# Snip_MCU.net
KiCad netlist of a schematic drawn in Altium Designer
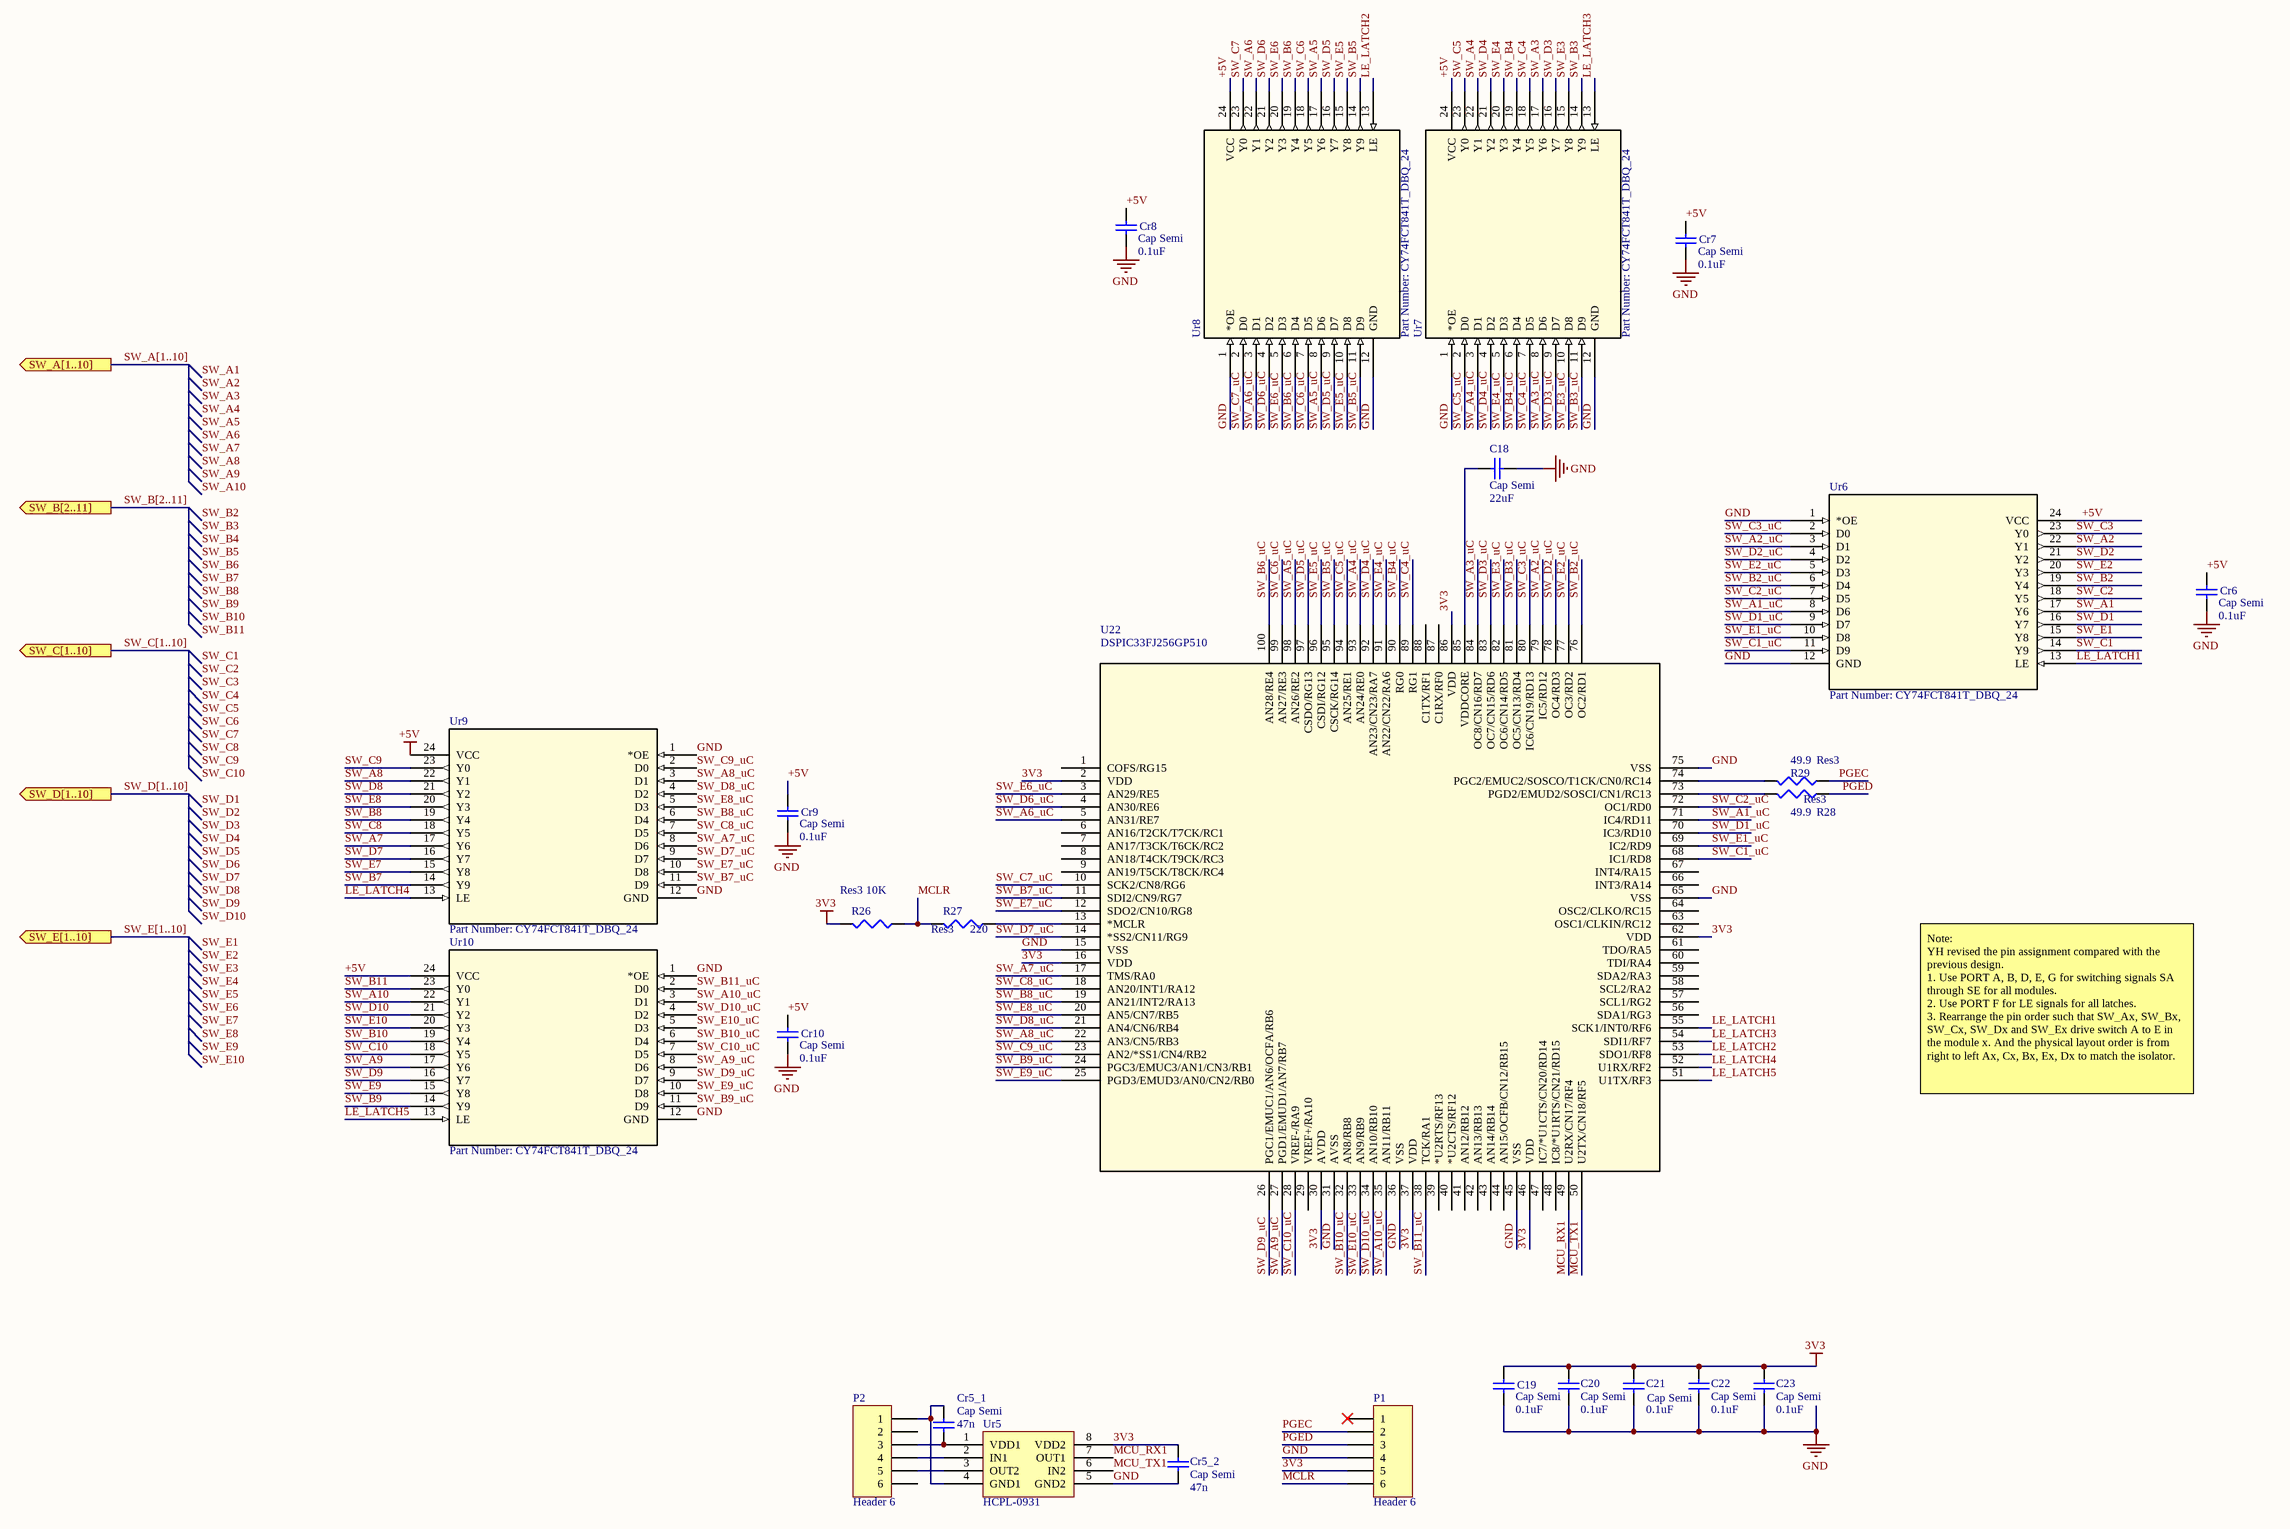
[diagram p0: Snip_MCU.SchDoc]

(export (version "E")
  (design (tool "Eeschema 10.0.6"))
  (components
    (comp (ref "C18")
      (value "Cap Semi")
      (footprint "0805")
      (description "Capacitor (Semiconductor SIM Model)")
      (fields (field (name "ALTIUM_VALUE") "22uF") (field (name "PUBLISHER") "Altium Limited"))
      (libsource (lib "SCMLI_V3_1") (part "Cap Semi"))
    )
    (comp (ref "C19")
      (value "Cap Semi")
      (footprint "1608[0603]")
      (description "Capacitor (Semiconductor SIM Model)")
      (fields (field (name "ALTIUM_VALUE") "0.1uF") (field (name "PUBLISHER") "Altium Limited"))
      (libsource (lib "Miscellaneous Devices") (part "Cap Semi"))
    )
    (comp (ref "C20")
      (value "Cap Semi")
      (footprint "1608[0603]")
      (description "Capacitor (Semiconductor SIM Model)")
      (fields (field (name "ALTIUM_VALUE") "0.1uF") (field (name "PUBLISHER") "Altium Limited"))
      (libsource (lib "Miscellaneous Devices") (part "Cap Semi"))
    )
    (comp (ref "C21")
      (value "Cap Semi")
      (footprint "1608[0603]")
      (description "Capacitor (Semiconductor SIM Model)")
      (fields (field (name "ALTIUM_VALUE") "0.1uF") (field (name "PUBLISHER") "Altium Limited"))
      (libsource (lib "Miscellaneous Devices") (part "Cap Semi"))
    )
    (comp (ref "C22")
      (value "Cap Semi")
      (footprint "1608[0603]")
      (description "Capacitor (Semiconductor SIM Model)")
      (fields (field (name "ALTIUM_VALUE") "0.1uF") (field (name "PUBLISHER") "Altium Limited"))
      (libsource (lib "Miscellaneous Devices") (part "Cap Semi"))
    )
    (comp (ref "C23")
      (value "Cap Semi")
      (footprint "1608[0603]")
      (description "Capacitor (Semiconductor SIM Model)")
      (fields (field (name "ALTIUM_VALUE") "0.1uF") (field (name "PUBLISHER") "Altium Limited"))
      (libsource (lib "Miscellaneous Devices") (part "Cap Semi"))
    )
    (comp (ref "Cr5_1")
      (value "Cap Semi")
      (footprint "C1206")
      (description "Capacitor (Semiconductor SIM Model)")
      (fields (field (name "ALTIUM_VALUE") "47n") (field (name "PUBLISHER") "Altium Limited"))
      (libsource (lib "SCMLI_V3_1") (part "Cap Semi"))
    )
    (comp (ref "Cr5_2")
      (value "Cap Semi")
      (footprint "C1206")
      (description "Capacitor (Semiconductor SIM Model)")
      (fields (field (name "ALTIUM_VALUE") "47n") (field (name "PUBLISHER") "Altium Limited"))
      (libsource (lib "SCMLI_V3_1") (part "Cap Semi"))
    )
    (comp (ref "Cr6")
      (value "Cap Semi")
      (footprint "1608[0603]")
      (description "Capacitor (Semiconductor SIM Model)")
      (fields (field (name "ALTIUM_VALUE") "0.1uF") (field (name "PUBLISHER") "Altium Limited"))
      (libsource (lib "Miscellaneous Devices") (part "Cap Semi"))
    )
    (comp (ref "Cr7")
      (value "Cap Semi")
      (footprint "1608[0603]")
      (description "Capacitor (Semiconductor SIM Model)")
      (fields (field (name "ALTIUM_VALUE") "0.1uF") (field (name "PUBLISHER") "Altium Limited"))
      (libsource (lib "Miscellaneous Devices") (part "Cap Semi"))
    )
    (comp (ref "Cr8")
      (value "Cap Semi")
      (footprint "1608[0603]")
      (description "Capacitor (Semiconductor SIM Model)")
      (fields (field (name "ALTIUM_VALUE") "0.1uF") (field (name "PUBLISHER") "Altium Limited"))
      (libsource (lib "Miscellaneous Devices") (part "Cap Semi"))
    )
    (comp (ref "Cr9")
      (value "Cap Semi")
      (footprint "1608[0603]")
      (description "Capacitor (Semiconductor SIM Model)")
      (fields (field (name "ALTIUM_VALUE") "0.1uF") (field (name "PUBLISHER") "Altium Limited"))
      (libsource (lib "Miscellaneous Devices") (part "Cap Semi"))
    )
    (comp (ref "Cr10")
      (value "Cap Semi")
      (footprint "1608[0603]")
      (description "Capacitor (Semiconductor SIM Model)")
      (fields (field (name "ALTIUM_VALUE") "0.1uF") (field (name "PUBLISHER") "Altium Limited"))
      (libsource (lib "Miscellaneous Devices") (part "Cap Semi"))
    )
    (comp (ref "P1")
      (value "Header 6")
      (footprint "HDR1X6")
      (description "Header, 6-Pin")
      (fields (field (name "PUBLISHER") "Altium Limited"))
      (libsource (lib "Miscellaneous Connectors") (part "Header 6"))
    )
    (comp (ref "P2")
      (value "Header 6")
      (footprint "HDR1X6")
      (description "Header, 6-Pin")
      (fields (field (name "PUBLISHER") "Altium Limited"))
      (libsource (lib "SCMLI_V3_1") (part "Header 6"))
    )
    (comp (ref "R26")
      (value "Res3")
      (footprint "J1-0603")
      (description "Resistor")
      (fields (field (name "ALTIUM_VALUE") "10K") (field (name "PUBLISHER") "Altium Limited"))
      (libsource (lib "Miscellaneous Devices") (part "Res3"))
    )
    (comp (ref "R27")
      (value "Res3")
      (footprint "J1-0603")
      (description "Resistor")
      (fields (field (name "ALTIUM_VALUE") "220") (field (name "PUBLISHER") "Altium Limited"))
      (libsource (lib "Miscellaneous Devices") (part "Res3"))
    )
    (comp (ref "R28")
      (value "Res3")
      (footprint "J1-0603")
      (description "Resistor")
      (fields (field (name "ALTIUM_VALUE") "49.9") (field (name "PUBLISHER") "Altium Limited"))
      (libsource (lib "Miscellaneous Devices") (part "Res3"))
    )
    (comp (ref "R29")
      (value "Res3")
      (footprint "J1-0603")
      (description "Resistor")
      (fields (field (name "ALTIUM_VALUE") "49.9") (field (name "PUBLISHER") "Altium Limited"))
      (libsource (lib "Miscellaneous Devices") (part "Res3"))
    )
    (comp (ref "U22")
      (value "DSPIC33FJ256GP510")
      (footprint "TQFP100_12x12MC-")
      (description "No Description Available")
      (fields (field (name "COPYRIGHT") "Copyright (C) 2018 Accelerated Designs. All rights reserved"))
      (libsource (lib "SCMLI_V3_1") (part "DSPIC33FJ256GP510"))
    )
    (comp (ref "Ur5")
      (value "HCPL-0931")
      (footprint "SOIC-8")
      (libsource (lib "SCMLI_V3_1") (part "HCPL-0931"))
    )
    (comp (ref "Ur6")
      (value "Part Number: CY74FCT841T_DBQ_24")
      (footprint "DBQ24")
      (description "10-Bit Bus-Interface D-Type Latches with 3-State Outputs")
      (fields
        (field (name "MANUFACTURER") "Texas Instruments")
        (field (name "GENERIC_PART_NUMBER") "CY74FCT841T")
        (field (name "COPYRIGHT") "Copyright (C) 2018 Accelerated Designs. All rights reserved")
      )
      (libsource (lib "") (part "CY74FCT841T_DBQ__2"))
    )
    (comp (ref "Ur7")
      (value "Part Number: CY74FCT841T_DBQ_24")
      (footprint "DBQ24")
      (description "10-Bit Bus-Interface D-Type Latches with 3-State Outputs")
      (fields
        (field (name "MANUFACTURER") "Texas Instruments")
        (field (name "GENERIC_PART_NUMBER") "CY74FCT841T")
        (field (name "COPYRIGHT") "Copyright (C) 2018 Accelerated Designs. All rights reserved")
      )
      (libsource (lib "") (part "CY74FCT841T_DBQ__1"))
    )
    (comp (ref "Ur8")
      (value "Part Number: CY74FCT841T_DBQ_24")
      (footprint "DBQ24")
      (description "10-Bit Bus-Interface D-Type Latches with 3-State Outputs")
      (fields
        (field (name "MANUFACTURER") "Texas Instruments")
        (field (name "GENERIC_PART_NUMBER") "CY74FCT841T")
        (field (name "COPYRIGHT") "Copyright (C) 2018 Accelerated Designs. All rights reserved")
      )
      (libsource (lib "") (part "CY74FCT841T_DBQ__1"))
    )
    (comp (ref "Ur9")
      (value "Part Number: CY74FCT841T_DBQ_24")
      (footprint "DBQ24")
      (description "10-Bit Bus-Interface D-Type Latches with 3-State Outputs")
      (fields
        (field (name "MANUFACTURER") "Texas Instruments")
        (field (name "GENERIC_PART_NUMBER") "CY74FCT841T")
        (field (name "COPYRIGHT") "Copyright (C) 2018 Accelerated Designs. All rights reserved")
      )
      (libsource (lib "SCMLI_V3_1") (part "CY74FCT841T_DBQ_"))
    )
    (comp (ref "Ur10")
      (value "Part Number: CY74FCT841T_DBQ_24")
      (footprint "DBQ24")
      (description "10-Bit Bus-Interface D-Type Latches with 3-State Outputs")
      (fields
        (field (name "MANUFACTURER") "Texas Instruments")
        (field (name "GENERIC_PART_NUMBER") "CY74FCT841T")
        (field (name "COPYRIGHT") "Copyright (C) 2018 Accelerated Designs. All rights reserved")
      )
      (libsource (lib "SCMLI_V3_1") (part "CY74FCT841T_DBQ_"))
    )
  )
  (nets
    (net (code "1") (name "+5V") (class "Default")
      (node (ref "Cr10") (pin "2") (pinfunction "2_2") (pintype "passive"))
      (node (ref "Cr6") (pin "2") (pinfunction "2_2") (pintype "passive"))
      (node (ref "Cr7") (pin "2") (pinfunction "2_2") (pintype "passive"))
      (node (ref "Cr8") (pin "2") (pinfunction "2_2") (pintype "passive"))
      (node (ref "Cr9") (pin "2") (pinfunction "2_2") (pintype "passive"))
      (node (ref "Ur10") (pin "24") (pinfunction "VCC_24") (pintype "power_in"))
      (node (ref "Ur6") (pin "24") (pinfunction "VCC_24") (pintype "power_in"))
      (node (ref "Ur7") (pin "24") (pinfunction "VCC_24") (pintype "power_in"))
      (node (ref "Ur8") (pin "24") (pinfunction "VCC_24") (pintype "power_in"))
      (node (ref "Ur9") (pin "24") (pinfunction "VCC_24") (pintype "power_in"))
    )
    (net (code "2") (name "/LE_LATCH1") (class "Default")
      (node (ref "U22") (pin "55") (pinfunction "SCK1/INT0/RF6_55") (pintype "passive"))
      (node (ref "Ur6") (pin "13") (pinfunction "LE_13") (pintype "input"))
    )
    (net (code "3") (name "/LE_LATCH2") (class "Default")
      (node (ref "U22") (pin "53") (pinfunction "SDO1/RF8_53") (pintype "passive"))
      (node (ref "Ur8") (pin "13") (pinfunction "LE_13") (pintype "input"))
    )
    (net (code "4") (name "/LE_LATCH3") (class "Default")
      (node (ref "U22") (pin "54") (pinfunction "SDI1/RF7_54") (pintype "passive"))
      (node (ref "Ur7") (pin "13") (pinfunction "LE_13") (pintype "input"))
    )
    (net (code "5") (name "/LE_LATCH4") (class "Default")
      (node (ref "U22") (pin "52") (pinfunction "U1RX/RF2_52") (pintype "passive"))
      (node (ref "Ur9") (pin "13") (pinfunction "LE_13") (pintype "input"))
    )
    (net (code "6") (name "/LE_LATCH5") (class "Default")
      (node (ref "U22") (pin "51") (pinfunction "U1TX/RF3_51") (pintype "passive"))
      (node (ref "Ur10") (pin "13") (pinfunction "LE_13") (pintype "input"))
    )
    (net (code "7") (name "/MCLR") (class "Default")
      (node (ref "P1") (pin "6") (pinfunction "6_6") (pintype "passive"))
      (node (ref "R26") (pin "1") (pinfunction "1_1") (pintype "passive"))
      (node (ref "R27") (pin "2") (pinfunction "2_2") (pintype "passive"))
    )
    (net (code "8") (name "/MCU_RX1") (class "Default")
      (node (ref "U22") (pin "49") (pinfunction "U2RX/CN17/RF4_49") (pintype "passive"))
      (node (ref "Ur5") (pin "7") (pinfunction "OUT1_7") (pintype "passive"))
    )
    (net (code "9") (name "/MCU_TX1") (class "Default")
      (node (ref "U22") (pin "50") (pinfunction "U2TX/CN18/RF5_50") (pintype "passive"))
      (node (ref "Ur5") (pin "6") (pinfunction "IN2_6") (pintype "passive"))
    )
    (net (code "10") (name "/PGEC") (class "Default")
      (node (ref "P1") (pin "2") (pinfunction "2_2") (pintype "passive"))
      (node (ref "R29") (pin "1") (pinfunction "1_1") (pintype "passive"))
    )
    (net (code "11") (name "/PGED") (class "Default")
      (node (ref "P1") (pin "3") (pinfunction "3_3") (pintype "passive"))
      (node (ref "R28") (pin "1") (pinfunction "1_1") (pintype "passive"))
    )
    (net (code "12") (name "/SW_A1") (class "Default")
      (node (ref "Ur6") (pin "17") (pinfunction "Y6_17") (pintype "output"))
    )
    (net (code "13") (name "/SW_A1_uC") (class "Default")
      (node (ref "U22") (pin "71") (pinfunction "IC4/RD11_71") (pintype "passive"))
      (node (ref "Ur6") (pin "8") (pinfunction "D6_8") (pintype "input"))
    )
    (net (code "14") (name "/SW_A2") (class "Default")
      (node (ref "Ur6") (pin "22") (pinfunction "Y1_22") (pintype "output"))
    )
    (net (code "15") (name "/SW_A2_uC") (class "Default")
      (node (ref "U22") (pin "79") (pinfunction "IC5/RD12_79") (pintype "passive"))
      (node (ref "Ur6") (pin "3") (pinfunction "D1_3") (pintype "input"))
    )
    (net (code "16") (name "/SW_A3") (class "Default")
      (node (ref "Ur7") (pin "17") (pinfunction "Y6_17") (pintype "output"))
    )
    (net (code "17") (name "/SW_A3_uC") (class "Default")
      (node (ref "U22") (pin "84") (pinfunction "OC8/CN16/RD7_84") (pintype "passive"))
      (node (ref "Ur7") (pin "8") (pinfunction "D6_8") (pintype "input"))
    )
    (net (code "18") (name "/SW_A4") (class "Default")
      (node (ref "Ur7") (pin "22") (pinfunction "Y1_22") (pintype "output"))
    )
    (net (code "19") (name "/SW_A4_uC") (class "Default")
      (node (ref "U22") (pin "93") (pinfunction "AN24/RE0_93") (pintype "passive"))
      (node (ref "Ur7") (pin "3") (pinfunction "D1_3") (pintype "input"))
    )
    (net (code "20") (name "/SW_A5") (class "Default")
      (node (ref "Ur8") (pin "17") (pinfunction "Y6_17") (pintype "output"))
    )
    (net (code "21") (name "/SW_A5_uC") (class "Default")
      (node (ref "U22") (pin "98") (pinfunction "AN26/RE2_98") (pintype "passive"))
      (node (ref "Ur8") (pin "8") (pinfunction "D6_8") (pintype "input"))
    )
    (net (code "22") (name "/SW_A6") (class "Default")
      (node (ref "Ur8") (pin "22") (pinfunction "Y1_22") (pintype "output"))
    )
    (net (code "23") (name "/SW_A6_uC") (class "Default")
      (node (ref "U22") (pin "5") (pinfunction "AN31/RE7_5") (pintype "passive"))
      (node (ref "Ur8") (pin "3") (pinfunction "D1_3") (pintype "input"))
    )
    (net (code "24") (name "/SW_A7") (class "Default")
      (node (ref "Ur9") (pin "17") (pinfunction "Y6_17") (pintype "output"))
    )
    (net (code "25") (name "/SW_A7_uC") (class "Default")
      (node (ref "U22") (pin "17") (pinfunction "TMS/RA0_17") (pintype "passive"))
      (node (ref "Ur9") (pin "8") (pinfunction "D6_8") (pintype "input"))
    )
    (net (code "26") (name "/SW_A8") (class "Default")
      (node (ref "Ur9") (pin "22") (pinfunction "Y1_22") (pintype "output"))
    )
    (net (code "27") (name "/SW_A8_uC") (class "Default")
      (node (ref "U22") (pin "22") (pinfunction "AN3/CN5/RB3_22") (pintype "passive"))
      (node (ref "Ur9") (pin "3") (pinfunction "D1_3") (pintype "input"))
    )
    (net (code "28") (name "/SW_A9") (class "Default")
      (node (ref "Ur10") (pin "17") (pinfunction "Y6_17") (pintype "output"))
    )
    (net (code "29") (name "/SW_A9_uC") (class "Default")
      (node (ref "U22") (pin "27") (pinfunction "PGD1/EMUD1/AN7/RB7_27") (pintype "passive"))
      (node (ref "Ur10") (pin "8") (pinfunction "D6_8") (pintype "input"))
    )
    (net (code "30") (name "/SW_A10") (class "Default")
      (node (ref "Ur10") (pin "22") (pinfunction "Y1_22") (pintype "output"))
    )
    (net (code "31") (name "/SW_A10_uC") (class "Default")
      (node (ref "U22") (pin "35") (pinfunction "AN11/RB11_35") (pintype "passive"))
      (node (ref "Ur10") (pin "3") (pinfunction "D1_3") (pintype "input"))
    )
    (net (code "33") (name "/SW_B2") (class "Default")
      (node (ref "Ur6") (pin "19") (pinfunction "Y4_19") (pintype "output"))
    )
    (net (code "34") (name "/SW_B2_uC") (class "Default")
      (node (ref "U22") (pin "76") (pinfunction "OC2/RD1_76") (pintype "passive"))
      (node (ref "Ur6") (pin "6") (pinfunction "D4_6") (pintype "input"))
    )
    (net (code "35") (name "/SW_B3") (class "Default")
      (node (ref "Ur7") (pin "14") (pinfunction "Y9_14") (pintype "output"))
    )
    (net (code "36") (name "/SW_B3_uC") (class "Default")
      (node (ref "U22") (pin "81") (pinfunction "OC5/CN13/RD4_81") (pintype "passive"))
      (node (ref "Ur7") (pin "11") (pinfunction "D9_11") (pintype "input"))
    )
    (net (code "37") (name "/SW_B4") (class "Default")
      (node (ref "Ur7") (pin "19") (pinfunction "Y4_19") (pintype "output"))
    )
    (net (code "38") (name "/SW_B4_uC") (class "Default")
      (node (ref "U22") (pin "90") (pinfunction "RG0_90") (pintype "passive"))
      (node (ref "Ur7") (pin "6") (pinfunction "D4_6") (pintype "input"))
    )
    (net (code "39") (name "/SW_B5") (class "Default")
      (node (ref "Ur8") (pin "14") (pinfunction "Y9_14") (pintype "output"))
    )
    (net (code "40") (name "/SW_B5_uC") (class "Default")
      (node (ref "U22") (pin "95") (pinfunction "CSCK/RG14_95") (pintype "passive"))
      (node (ref "Ur8") (pin "11") (pinfunction "D9_11") (pintype "input"))
    )
    (net (code "41") (name "/SW_B6") (class "Default")
      (node (ref "Ur8") (pin "19") (pinfunction "Y4_19") (pintype "output"))
    )
    (net (code "42") (name "/SW_B6_uC") (class "Default")
      (node (ref "U22") (pin "100") (pinfunction "AN28/RE4_100") (pintype "passive"))
      (node (ref "Ur8") (pin "6") (pinfunction "D4_6") (pintype "input"))
    )
    (net (code "43") (name "/SW_B7") (class "Default")
      (node (ref "Ur9") (pin "14") (pinfunction "Y9_14") (pintype "output"))
    )
    (net (code "44") (name "/SW_B7_uC") (class "Default")
      (node (ref "U22") (pin "11") (pinfunction "SDI2/CN9/RG7_11") (pintype "passive"))
      (node (ref "Ur9") (pin "11") (pinfunction "D9_11") (pintype "input"))
    )
    (net (code "45") (name "/SW_B8") (class "Default")
      (node (ref "Ur9") (pin "19") (pinfunction "Y4_19") (pintype "output"))
    )
    (net (code "46") (name "/SW_B8_uC") (class "Default")
      (node (ref "U22") (pin "19") (pinfunction "AN21/INT2/RA13_19") (pintype "passive"))
      (node (ref "Ur9") (pin "6") (pinfunction "D4_6") (pintype "input"))
    )
    (net (code "47") (name "/SW_B9") (class "Default")
      (node (ref "Ur10") (pin "14") (pinfunction "Y9_14") (pintype "output"))
    )
    (net (code "48") (name "/SW_B9_uC") (class "Default")
      (node (ref "U22") (pin "24") (pinfunction "PGC3/EMUC3/AN1/CN3/RB1_24") (pintype "passive"))
      (node (ref "Ur10") (pin "11") (pinfunction "D9_11") (pintype "input"))
    )
    (net (code "49") (name "/SW_B10") (class "Default")
      (node (ref "Ur10") (pin "19") (pinfunction "Y4_19") (pintype "output"))
    )
    (net (code "50") (name "/SW_B10_uC") (class "Default")
      (node (ref "U22") (pin "32") (pinfunction "AN8/RB8_32") (pintype "passive"))
      (node (ref "Ur10") (pin "6") (pinfunction "D4_6") (pintype "input"))
    )
    (net (code "51") (name "/SW_B11") (class "Default")
      (node (ref "Ur10") (pin "23") (pinfunction "Y0_23") (pintype "output"))
    )
    (net (code "52") (name "/SW_B11_uC") (class "Default")
      (node (ref "U22") (pin "38") (pinfunction "TCK/RA1_38") (pintype "passive"))
      (node (ref "Ur10") (pin "2") (pinfunction "D0_2") (pintype "input"))
    )
    (net (code "54") (name "/SW_C1") (class "Default")
      (node (ref "Ur6") (pin "14") (pinfunction "Y9_14") (pintype "output"))
    )
    (net (code "55") (name "/SW_C1_uC") (class "Default")
      (node (ref "U22") (pin "68") (pinfunction "IC1/RD8_68") (pintype "passive"))
      (node (ref "Ur6") (pin "11") (pinfunction "D9_11") (pintype "input"))
    )
    (net (code "56") (name "/SW_C2") (class "Default")
      (node (ref "Ur6") (pin "18") (pinfunction "Y5_18") (pintype "output"))
    )
    (net (code "57") (name "/SW_C2_uC") (class "Default")
      (node (ref "U22") (pin "72") (pinfunction "OC1/RD0_72") (pintype "passive"))
      (node (ref "Ur6") (pin "7") (pinfunction "D5_7") (pintype "input"))
    )
    (net (code "58") (name "/SW_C3") (class "Default")
      (node (ref "Ur6") (pin "23") (pinfunction "Y0_23") (pintype "output"))
    )
    (net (code "59") (name "/SW_C3_uC") (class "Default")
      (node (ref "U22") (pin "80") (pinfunction "IC6/CN19/RD13_80") (pintype "passive"))
      (node (ref "Ur6") (pin "2") (pinfunction "D0_2") (pintype "input"))
    )
    (net (code "60") (name "/SW_C4") (class "Default")
      (node (ref "Ur7") (pin "18") (pinfunction "Y5_18") (pintype "output"))
    )
    (net (code "61") (name "/SW_C4_uC") (class "Default")
      (node (ref "U22") (pin "89") (pinfunction "RG1_89") (pintype "passive"))
      (node (ref "Ur7") (pin "7") (pinfunction "D5_7") (pintype "input"))
    )
    (net (code "62") (name "/SW_C5") (class "Default")
      (node (ref "Ur7") (pin "23") (pinfunction "Y0_23") (pintype "output"))
    )
    (net (code "63") (name "/SW_C5_uC") (class "Default")
      (node (ref "U22") (pin "94") (pinfunction "AN25/RE1_94") (pintype "passive"))
      (node (ref "Ur7") (pin "2") (pinfunction "D0_2") (pintype "input"))
    )
    (net (code "64") (name "/SW_C6") (class "Default")
      (node (ref "Ur8") (pin "18") (pinfunction "Y5_18") (pintype "output"))
    )
    (net (code "65") (name "/SW_C6_uC") (class "Default")
      (node (ref "U22") (pin "99") (pinfunction "AN27/RE3_99") (pintype "passive"))
      (node (ref "Ur8") (pin "7") (pinfunction "D5_7") (pintype "input"))
    )
    (net (code "66") (name "/SW_C7") (class "Default")
      (node (ref "Ur8") (pin "23") (pinfunction "Y0_23") (pintype "output"))
    )
    (net (code "67") (name "/SW_C7_uC") (class "Default")
      (node (ref "U22") (pin "10") (pinfunction "SCK2/CN8/RG6_10") (pintype "passive"))
      (node (ref "Ur8") (pin "2") (pinfunction "D0_2") (pintype "input"))
    )
    (net (code "68") (name "/SW_C8") (class "Default")
      (node (ref "Ur9") (pin "18") (pinfunction "Y5_18") (pintype "output"))
    )
    (net (code "69") (name "/SW_C8_uC") (class "Default")
      (node (ref "U22") (pin "18") (pinfunction "AN20/INT1/RA12_18") (pintype "passive"))
      (node (ref "Ur9") (pin "7") (pinfunction "D5_7") (pintype "input"))
    )
    (net (code "70") (name "/SW_C9") (class "Default")
      (node (ref "Ur9") (pin "23") (pinfunction "Y0_23") (pintype "output"))
    )
    (net (code "71") (name "/SW_C9_uC") (class "Default")
      (node (ref "U22") (pin "23") (pinfunction "AN2/*SS1/CN4/RB2_23") (pintype "passive"))
      (node (ref "Ur9") (pin "2") (pinfunction "D0_2") (pintype "input"))
    )
    (net (code "72") (name "/SW_C10") (class "Default")
      (node (ref "Ur10") (pin "18") (pinfunction "Y5_18") (pintype "output"))
    )
    (net (code "73") (name "/SW_C10_uC") (class "Default")
      (node (ref "U22") (pin "28") (pinfunction "VREF-/RA9_28") (pintype "passive"))
      (node (ref "Ur10") (pin "7") (pinfunction "D5_7") (pintype "input"))
    )
    (net (code "75") (name "/SW_D1") (class "Default")
      (node (ref "Ur6") (pin "16") (pinfunction "Y7_16") (pintype "output"))
    )
    (net (code "76") (name "/SW_D1_uC") (class "Default")
      (node (ref "U22") (pin "70") (pinfunction "IC3/RD10_70") (pintype "passive"))
      (node (ref "Ur6") (pin "9") (pinfunction "D7_9") (pintype "input"))
    )
    (net (code "77") (name "/SW_D2") (class "Default")
      (node (ref "Ur6") (pin "21") (pinfunction "Y2_21") (pintype "output"))
    )
    (net (code "78") (name "/SW_D2_uC") (class "Default")
      (node (ref "U22") (pin "78") (pinfunction "OC4/RD3_78") (pintype "passive"))
      (node (ref "Ur6") (pin "4") (pinfunction "D2_4") (pintype "input"))
    )
    (net (code "79") (name "/SW_D3") (class "Default")
      (node (ref "Ur7") (pin "16") (pinfunction "Y7_16") (pintype "output"))
    )
    (net (code "80") (name "/SW_D3_uC") (class "Default")
      (node (ref "U22") (pin "83") (pinfunction "OC7/CN15/RD6_83") (pintype "passive"))
      (node (ref "Ur7") (pin "9") (pinfunction "D7_9") (pintype "input"))
    )
    (net (code "81") (name "/SW_D4") (class "Default")
      (node (ref "Ur7") (pin "21") (pinfunction "Y2_21") (pintype "output"))
    )
    (net (code "82") (name "/SW_D4_uC") (class "Default")
      (node (ref "U22") (pin "92") (pinfunction "AN23/CN23/RA7_92") (pintype "passive"))
      (node (ref "Ur7") (pin "4") (pinfunction "D2_4") (pintype "input"))
    )
    (net (code "83") (name "/SW_D5") (class "Default")
      (node (ref "Ur8") (pin "16") (pinfunction "Y7_16") (pintype "output"))
    )
    (net (code "84") (name "/SW_D5_uC") (class "Default")
      (node (ref "U22") (pin "97") (pinfunction "CSDO/RG13_97") (pintype "passive"))
      (node (ref "Ur8") (pin "9") (pinfunction "D7_9") (pintype "input"))
    )
    (net (code "85") (name "/SW_D6") (class "Default")
      (node (ref "Ur8") (pin "21") (pinfunction "Y2_21") (pintype "output"))
    )
    (net (code "86") (name "/SW_D6_uC") (class "Default")
      (node (ref "U22") (pin "4") (pinfunction "AN30/RE6_4") (pintype "passive"))
      (node (ref "Ur8") (pin "4") (pinfunction "D2_4") (pintype "input"))
    )
    (net (code "87") (name "/SW_D7") (class "Default")
      (node (ref "Ur9") (pin "16") (pinfunction "Y7_16") (pintype "output"))
    )
    (net (code "88") (name "/SW_D7_uC") (class "Default")
      (node (ref "U22") (pin "14") (pinfunction "*SS2/CN11/RG9_14") (pintype "passive"))
      (node (ref "Ur9") (pin "9") (pinfunction "D7_9") (pintype "input"))
    )
    (net (code "89") (name "/SW_D8") (class "Default")
      (node (ref "Ur9") (pin "21") (pinfunction "Y2_21") (pintype "output"))
    )
    (net (code "90") (name "/SW_D8_uC") (class "Default")
      (node (ref "U22") (pin "21") (pinfunction "AN4/CN6/RB4_21") (pintype "passive"))
      (node (ref "Ur9") (pin "4") (pinfunction "D2_4") (pintype "input"))
    )
    (net (code "91") (name "/SW_D9") (class "Default")
      (node (ref "Ur10") (pin "16") (pinfunction "Y7_16") (pintype "output"))
    )
    (net (code "92") (name "/SW_D9_uC") (class "Default")
      (node (ref "U22") (pin "26") (pinfunction "PGC1/EMUC1/AN6/OCFA/RB6_26") (pintype "passive"))
      (node (ref "Ur10") (pin "9") (pinfunction "D7_9") (pintype "input"))
    )
    (net (code "93") (name "/SW_D10") (class "Default")
      (node (ref "Ur10") (pin "21") (pinfunction "Y2_21") (pintype "output"))
    )
    (net (code "94") (name "/SW_D10_uC") (class "Default")
      (node (ref "U22") (pin "34") (pinfunction "AN10/RB10_34") (pintype "passive"))
      (node (ref "Ur10") (pin "4") (pinfunction "D2_4") (pintype "input"))
    )
    (net (code "96") (name "/SW_E1") (class "Default")
      (node (ref "Ur6") (pin "15") (pinfunction "Y8_15") (pintype "output"))
    )
    (net (code "97") (name "/SW_E1_uC") (class "Default")
      (node (ref "U22") (pin "69") (pinfunction "IC2/RD9_69") (pintype "passive"))
      (node (ref "Ur6") (pin "10") (pinfunction "D8_10") (pintype "input"))
    )
    (net (code "98") (name "/SW_E2") (class "Default")
      (node (ref "Ur6") (pin "20") (pinfunction "Y3_20") (pintype "output"))
    )
    (net (code "99") (name "/SW_E2_uC") (class "Default")
      (node (ref "U22") (pin "77") (pinfunction "OC3/RD2_77") (pintype "passive"))
      (node (ref "Ur6") (pin "5") (pinfunction "D3_5") (pintype "input"))
    )
    (net (code "100") (name "/SW_E3") (class "Default")
      (node (ref "Ur7") (pin "15") (pinfunction "Y8_15") (pintype "output"))
    )
    (net (code "101") (name "/SW_E3_uC") (class "Default")
      (node (ref "U22") (pin "82") (pinfunction "OC6/CN14/RD5_82") (pintype "passive"))
      (node (ref "Ur7") (pin "10") (pinfunction "D8_10") (pintype "input"))
    )
    (net (code "102") (name "/SW_E4") (class "Default")
      (node (ref "Ur7") (pin "20") (pinfunction "Y3_20") (pintype "output"))
    )
    (net (code "103") (name "/SW_E4_uC") (class "Default")
      (node (ref "U22") (pin "91") (pinfunction "AN22/CN22/RA6_91") (pintype "passive"))
      (node (ref "Ur7") (pin "5") (pinfunction "D3_5") (pintype "input"))
    )
    (net (code "104") (name "/SW_E5") (class "Default")
      (node (ref "Ur8") (pin "15") (pinfunction "Y8_15") (pintype "output"))
    )
    (net (code "105") (name "/SW_E5_uC") (class "Default")
      (node (ref "U22") (pin "96") (pinfunction "CSDI/RG12_96") (pintype "passive"))
      (node (ref "Ur8") (pin "10") (pinfunction "D8_10") (pintype "input"))
    )
    (net (code "106") (name "/SW_E6") (class "Default")
      (node (ref "Ur8") (pin "20") (pinfunction "Y3_20") (pintype "output"))
    )
    (net (code "107") (name "/SW_E6_uC") (class "Default")
      (node (ref "U22") (pin "3") (pinfunction "AN29/RE5_3") (pintype "passive"))
      (node (ref "Ur8") (pin "5") (pinfunction "D3_5") (pintype "input"))
    )
    (net (code "108") (name "/SW_E7") (class "Default")
      (node (ref "Ur9") (pin "15") (pinfunction "Y8_15") (pintype "output"))
    )
    (net (code "109") (name "/SW_E7_uC") (class "Default")
      (node (ref "U22") (pin "12") (pinfunction "SDO2/CN10/RG8_12") (pintype "passive"))
      (node (ref "Ur9") (pin "10") (pinfunction "D8_10") (pintype "input"))
    )
    (net (code "110") (name "/SW_E8") (class "Default")
      (node (ref "Ur9") (pin "20") (pinfunction "Y3_20") (pintype "output"))
    )
    (net (code "111") (name "/SW_E8_uC") (class "Default")
      (node (ref "U22") (pin "20") (pinfunction "AN5/CN7/RB5_20") (pintype "passive"))
      (node (ref "Ur9") (pin "5") (pinfunction "D3_5") (pintype "input"))
    )
    (net (code "112") (name "/SW_E9") (class "Default")
      (node (ref "Ur10") (pin "15") (pinfunction "Y8_15") (pintype "output"))
    )
    (net (code "113") (name "/SW_E9_uC") (class "Default")
      (node (ref "U22") (pin "25") (pinfunction "PGD3/EMUD3/AN0/CN2/RB0_25") (pintype "passive"))
      (node (ref "Ur10") (pin "10") (pinfunction "D8_10") (pintype "input"))
    )
    (net (code "114") (name "/SW_E10") (class "Default")
      (node (ref "Ur10") (pin "20") (pinfunction "Y3_20") (pintype "output"))
    )
    (net (code "115") (name "/SW_E10_uC") (class "Default")
      (node (ref "U22") (pin "33") (pinfunction "AN9/RB9_33") (pintype "passive"))
      (node (ref "Ur10") (pin "5") (pinfunction "D3_5") (pintype "input"))
    )
    (net (code "117") (name "3V3") (class "Default")
      (node (ref "C19") (pin "2") (pinfunction "2_2") (pintype "passive"))
      (node (ref "C20") (pin "2") (pinfunction "2_2") (pintype "passive"))
      (node (ref "C21") (pin "2") (pinfunction "2_2") (pintype "passive"))
      (node (ref "C22") (pin "2") (pinfunction "2_2") (pintype "passive"))
      (node (ref "C23") (pin "2") (pinfunction "2_2") (pintype "passive"))
      (node (ref "Cr5_2") (pin "2") (pinfunction "2_2") (pintype "passive"))
      (node (ref "P1") (pin "5") (pinfunction "5_5") (pintype "passive"))
      (node (ref "R26") (pin "2") (pinfunction "2_2") (pintype "passive"))
      (node (ref "U22") (pin "16") (pinfunction "VDD_16") (pintype "passive"))
      (node (ref "U22") (pin "2") (pinfunction "VDD_2") (pintype "passive"))
      (node (ref "U22") (pin "30") (pinfunction "AVDD_30") (pintype "passive"))
      (node (ref "U22") (pin "37") (pinfunction "VDD_37") (pintype "passive"))
      (node (ref "U22") (pin "46") (pinfunction "VDD_46") (pintype "passive"))
      (node (ref "U22") (pin "62") (pinfunction "VDD_62") (pintype "passive"))
      (node (ref "U22") (pin "86") (pinfunction "VDD_86") (pintype "passive"))
      (node (ref "Ur5") (pin "8") (pinfunction "VDD2_8") (pintype "passive"))
    )
    (net (code "118") (name "GND") (class "Default")
      (node (ref "C18") (pin "2") (pinfunction "2_2") (pintype "passive"))
      (node (ref "C19") (pin "1") (pinfunction "1_1") (pintype "passive"))
      (node (ref "C20") (pin "1") (pinfunction "1_1") (pintype "passive"))
      (node (ref "C21") (pin "1") (pinfunction "1_1") (pintype "passive"))
      (node (ref "C22") (pin "1") (pinfunction "1_1") (pintype "passive"))
      (node (ref "C23") (pin "1") (pinfunction "1_1") (pintype "passive"))
      (node (ref "Cr10") (pin "1") (pinfunction "1_1") (pintype "passive"))
      (node (ref "Cr5_2") (pin "1") (pinfunction "1_1") (pintype "passive"))
      (node (ref "Cr6") (pin "1") (pinfunction "1_1") (pintype "passive"))
      (node (ref "Cr7") (pin "1") (pinfunction "1_1") (pintype "passive"))
      (node (ref "Cr8") (pin "1") (pinfunction "1_1") (pintype "passive"))
      (node (ref "Cr9") (pin "1") (pinfunction "1_1") (pintype "passive"))
      (node (ref "P1") (pin "4") (pinfunction "4_4") (pintype "passive"))
      (node (ref "U22") (pin "15") (pinfunction "VSS_15") (pintype "passive"))
      (node (ref "U22") (pin "31") (pinfunction "AVSS_31") (pintype "passive"))
      (node (ref "U22") (pin "36") (pinfunction "VSS_36") (pintype "passive"))
      (node (ref "U22") (pin "45") (pinfunction "VSS_45") (pintype "passive"))
      (node (ref "U22") (pin "65") (pinfunction "VSS_65") (pintype "passive"))
      (node (ref "U22") (pin "75") (pinfunction "VSS_75") (pintype "passive"))
      (node (ref "Ur10") (pin "1") (pinfunction "*OE_1") (pintype "input"))
      (node (ref "Ur10") (pin "12") (pinfunction "GND_12") (pintype "power_in"))
      (node (ref "Ur5") (pin "5") (pinfunction "GND2_5") (pintype "passive"))
      (node (ref "Ur6") (pin "1") (pinfunction "*OE_1") (pintype "input"))
      (node (ref "Ur6") (pin "12") (pinfunction "GND_12") (pintype "power_in"))
      (node (ref "Ur7") (pin "1") (pinfunction "*OE_1") (pintype "input"))
      (node (ref "Ur7") (pin "12") (pinfunction "GND_12") (pintype "power_in"))
      (node (ref "Ur8") (pin "1") (pinfunction "*OE_1") (pintype "input"))
      (node (ref "Ur8") (pin "12") (pinfunction "GND_12") (pintype "power_in"))
      (node (ref "Ur9") (pin "1") (pinfunction "*OE_1") (pintype "input"))
      (node (ref "Ur9") (pin "12") (pinfunction "GND_12") (pintype "power_in"))
    )
    (net (code "119") (name "Net-(U22-*MCLR)") (class "Default")
      (node (ref "R27") (pin "1") (pinfunction "1_1") (pintype "passive"))
      (node (ref "U22") (pin "13") (pinfunction "*MCLR_13") (pintype "passive"))
    )
    (net (code "120") (name "Net-(U22-PGC2{slash}EMUC2{slash}SOSCO{slash}T1CK{slash}CN0{slash}RC14)") (class "Default")
      (node (ref "R29") (pin "2") (pinfunction "2_2") (pintype "passive"))
      (node (ref "U22") (pin "74") (pinfunction "PGC2/EMUC2/SOSCO/T1CK/CN0/RC14_74") (pintype "passive"))
    )
    (net (code "121") (name "Net-(U22-PGD2{slash}EMUD2{slash}SOSCI{slash}CN1{slash}RC13)") (class "Default")
      (node (ref "R28") (pin "2") (pinfunction "2_2") (pintype "passive"))
      (node (ref "U22") (pin "73") (pinfunction "PGD2/EMUD2/SOSCI/CN1/RC13_73") (pintype "passive"))
    )
    (net (code "122") (name "Net-(U22-VDDCORE)") (class "Default")
      (node (ref "C18") (pin "1") (pinfunction "1_1") (pintype "passive"))
      (node (ref "U22") (pin "85") (pinfunction "VDDCORE_85") (pintype "passive"))
    )
    (net (code "123") (name "Net-(Ur5-GND1)") (class "Default")
      (node (ref "Cr5_1") (pin "2") (pinfunction "2_2") (pintype "passive"))
      (node (ref "P2") (pin "1") (pinfunction "1_1") (pintype "passive"))
      (node (ref "Ur5") (pin "4") (pinfunction "GND1_4") (pintype "passive"))
    )
    (net (code "124") (name "Net-(Ur5-IN1)") (class "Default")
      (node (ref "P2") (pin "4") (pinfunction "4_4") (pintype "passive"))
      (node (ref "Ur5") (pin "2") (pinfunction "IN1_2") (pintype "passive"))
    )
    (net (code "125") (name "Net-(Ur5-OUT2)") (class "Default")
      (node (ref "P2") (pin "5") (pinfunction "5_5") (pintype "passive"))
      (node (ref "Ur5") (pin "3") (pinfunction "OUT2_3") (pintype "passive"))
    )
    (net (code "126") (name "Net-(Ur5-VDD1)") (class "Default")
      (node (ref "Cr5_1") (pin "1") (pinfunction "1_1") (pintype "passive"))
      (node (ref "P2") (pin "3") (pinfunction "3_3") (pintype "passive"))
      (node (ref "Ur5") (pin "1") (pinfunction "VDD1_1") (pintype "passive"))
    )
    (net (code "127") (name "unconnected-(P1-Pad1)") (class "Default")
      (node (ref "P1") (pin "1") (pinfunction "1_1") (pintype "passive+no_connect"))
    )
    (net (code "128") (name "unconnected-(P2-Pad2)") (class "Default")
      (node (ref "P2") (pin "2") (pinfunction "2_2") (pintype "passive"))
    )
    (net (code "129") (name "unconnected-(P2-Pad6)") (class "Default")
      (node (ref "P2") (pin "6") (pinfunction "6_6") (pintype "passive"))
    )
    (net (code "130") (name "unconnected-(U22-*U2CTS{slash}RF12-Pad40)") (class "Default")
      (node (ref "U22") (pin "40") (pinfunction "*U2CTS/RF12_40") (pintype "passive"))
    )
    (net (code "131") (name "unconnected-(U22-*U2RTS{slash}RF13-Pad39)") (class "Default")
      (node (ref "U22") (pin "39") (pinfunction "*U2RTS/RF13_39") (pintype "passive"))
    )
    (net (code "132") (name "unconnected-(U22-AN12{slash}RB12-Pad41)") (class "Default")
      (node (ref "U22") (pin "41") (pinfunction "AN12/RB12_41") (pintype "passive"))
    )
    (net (code "133") (name "unconnected-(U22-AN13{slash}RB13-Pad42)") (class "Default")
      (node (ref "U22") (pin "42") (pinfunction "AN13/RB13_42") (pintype "passive"))
    )
    (net (code "134") (name "unconnected-(U22-AN14{slash}RB14-Pad43)") (class "Default")
      (node (ref "U22") (pin "43") (pinfunction "AN14/RB14_43") (pintype "passive"))
    )
    (net (code "135") (name "unconnected-(U22-AN15{slash}OCFB{slash}CN12{slash}RB15-Pad44)") (class "Default")
      (node (ref "U22") (pin "44") (pinfunction "AN15/OCFB/CN12/RB15_44") (pintype "passive"))
    )
    (net (code "136") (name "unconnected-(U22-AN16{slash}T2CK{slash}T7CK{slash}RC1-Pad6)") (class "Default")
      (node (ref "U22") (pin "6") (pinfunction "AN16/T2CK/T7CK/RC1_6") (pintype "passive"))
    )
    (net (code "137") (name "unconnected-(U22-AN17{slash}T3CK{slash}T6CK{slash}RC2-Pad7)") (class "Default")
      (node (ref "U22") (pin "7") (pinfunction "AN17/T3CK/T6CK/RC2_7") (pintype "passive"))
    )
    (net (code "138") (name "unconnected-(U22-AN18{slash}T4CK{slash}T9CK{slash}RC3-Pad8)") (class "Default")
      (node (ref "U22") (pin "8") (pinfunction "AN18/T4CK/T9CK/RC3_8") (pintype "passive"))
    )
    (net (code "139") (name "unconnected-(U22-AN19{slash}T5CK{slash}T8CK{slash}RC4-Pad9)") (class "Default")
      (node (ref "U22") (pin "9") (pinfunction "AN19/T5CK/T8CK/RC4_9") (pintype "passive"))
    )
    (net (code "140") (name "unconnected-(U22-C1RX{slash}RF0-Pad87)") (class "Default")
      (node (ref "U22") (pin "87") (pinfunction "C1RX/RF0_87") (pintype "passive"))
    )
    (net (code "141") (name "unconnected-(U22-C1TX{slash}RF1-Pad88)") (class "Default")
      (node (ref "U22") (pin "88") (pinfunction "C1TX/RF1_88") (pintype "passive"))
    )
    (net (code "142") (name "unconnected-(U22-COFS{slash}RG15-Pad1)") (class "Default")
      (node (ref "U22") (pin "1") (pinfunction "COFS/RG15_1") (pintype "passive"))
    )
    (net (code "143") (name "unconnected-(U22-IC7{slash}*U1CTS{slash}CN20{slash}RD14-Pad47)") (class "Default")
      (node (ref "U22") (pin "47") (pinfunction "IC7/*U1CTS/CN20/RD14_47") (pintype "passive"))
    )
    (net (code "144") (name "unconnected-(U22-IC8{slash}*U1RTS{slash}CN21{slash}RD15-Pad48)") (class "Default")
      (node (ref "U22") (pin "48") (pinfunction "IC8/*U1RTS/CN21/RD15_48") (pintype "passive"))
    )
    (net (code "145") (name "unconnected-(U22-INT3{slash}RA14-Pad66)") (class "Default")
      (node (ref "U22") (pin "66") (pinfunction "INT3/RA14_66") (pintype "passive"))
    )
    (net (code "146") (name "unconnected-(U22-INT4{slash}RA15-Pad67)") (class "Default")
      (node (ref "U22") (pin "67") (pinfunction "INT4/RA15_67") (pintype "passive"))
    )
    (net (code "147") (name "unconnected-(U22-OSC1{slash}CLKIN{slash}RC12-Pad63)") (class "Default")
      (node (ref "U22") (pin "63") (pinfunction "OSC1/CLKIN/RC12_63") (pintype "passive"))
    )
    (net (code "148") (name "unconnected-(U22-OSC2{slash}CLKO{slash}RC15-Pad64)") (class "Default")
      (node (ref "U22") (pin "64") (pinfunction "OSC2/CLKO/RC15_64") (pintype "passive"))
    )
    (net (code "149") (name "unconnected-(U22-SCL1{slash}RG2-Pad57)") (class "Default")
      (node (ref "U22") (pin "57") (pinfunction "SCL1/RG2_57") (pintype "passive"))
    )
    (net (code "150") (name "unconnected-(U22-SCL2{slash}RA2-Pad58)") (class "Default")
      (node (ref "U22") (pin "58") (pinfunction "SCL2/RA2_58") (pintype "passive"))
    )
    (net (code "151") (name "unconnected-(U22-SDA1{slash}RG3-Pad56)") (class "Default")
      (node (ref "U22") (pin "56") (pinfunction "SDA1/RG3_56") (pintype "passive"))
    )
    (net (code "152") (name "unconnected-(U22-SDA2{slash}RA3-Pad59)") (class "Default")
      (node (ref "U22") (pin "59") (pinfunction "SDA2/RA3_59") (pintype "passive"))
    )
    (net (code "153") (name "unconnected-(U22-TDI{slash}RA4-Pad60)") (class "Default")
      (node (ref "U22") (pin "60") (pinfunction "TDI/RA4_60") (pintype "passive"))
    )
    (net (code "154") (name "unconnected-(U22-TDO{slash}RA5-Pad61)") (class "Default")
      (node (ref "U22") (pin "61") (pinfunction "TDO/RA5_61") (pintype "passive"))
    )
    (net (code "155") (name "unconnected-(U22-VREF+{slash}RA10-Pad29)") (class "Default")
      (node (ref "U22") (pin "29") (pinfunction "VREF+/RA10_29") (pintype "passive"))
    )
  )
)
